# e0-dev-v004.net
KiCad netlist of a schematic drawn in EAGLE
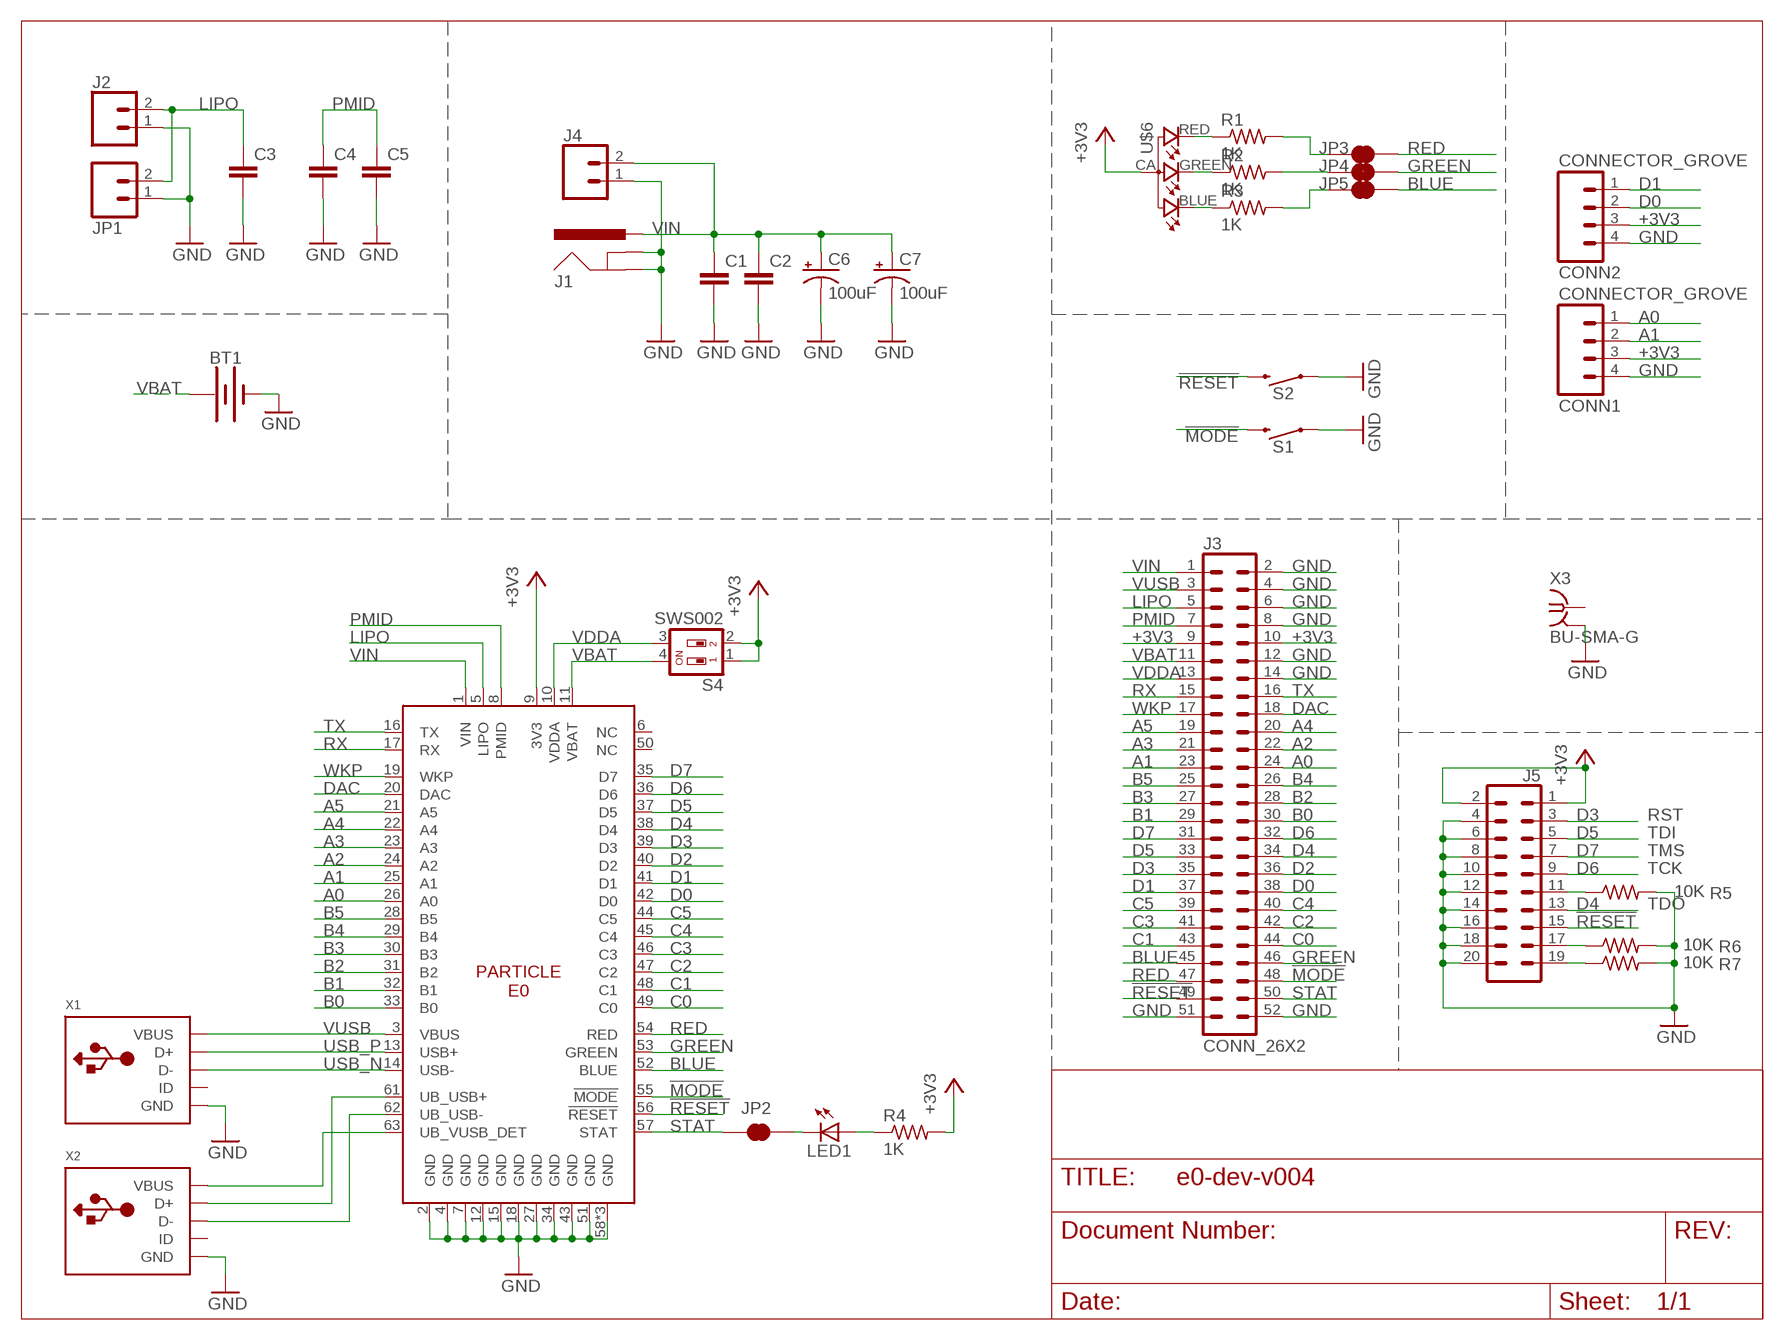
[diagram p0: schematic, sheet 1]

(export (version "E")
  (design (tool "Eeschema 10.0.6"))
  (components
    (comp (ref "BT1")
      (value "BATTERY-20MM_SMD")
      (footprint "eagle-import:BATTCON_20MM")
      (libsource (lib "eagle-import") (part "BATTERY-20MM_SMD"))
    )
    (comp (ref "C1")
      (value "C-EUC0805")
      (footprint "eagle-import:C0805")
      (libsource (lib "eagle-import") (part "C-EUC0805"))
    )
    (comp (ref "C2")
      (value "C-EUC0805")
      (footprint "eagle-import:C0805")
      (libsource (lib "eagle-import") (part "C-EUC0805"))
    )
    (comp (ref "C3")
      (value "C-EUC0805")
      (footprint "eagle-import:C0805")
      (libsource (lib "eagle-import") (part "C-EUC0805"))
    )
    (comp (ref "C4")
      (value "C-EUC0805")
      (footprint "eagle-import:C0805")
      (libsource (lib "eagle-import") (part "C-EUC0805"))
    )
    (comp (ref "C5")
      (value "C-EUC0805")
      (footprint "eagle-import:C0805")
      (libsource (lib "eagle-import") (part "C-EUC0805"))
    )
    (comp (ref "C6")
      (value "100uF")
      (footprint "eagle-import:PANASONIC_D")
      (libsource (lib "eagle-import") (part "100UF-POLAR-25V-20%(ELEC)"))
    )
    (comp (ref "C7")
      (value "100uF")
      (footprint "eagle-import:PANASONIC_D")
      (libsource (lib "eagle-import") (part "100UF-POLAR-25V-20%(ELEC)"))
    )
    (comp (ref "CONN1")
      (value "CONNECTOR_GROVE")
      (footprint "eagle-import:CONNCTOR_GROVE")
      (libsource (lib "eagle-import") (part "CONNECTOR_GROVE"))
    )
    (comp (ref "CONN2")
      (value "CONNECTOR_GROVE")
      (footprint "eagle-import:CONNCTOR_GROVE")
      (libsource (lib "eagle-import") (part "CONNECTOR_GROVE"))
    )
    (comp (ref "J1")
      (value "POWER_JACKSLT")
      (footprint "eagle-import:POWER_JACK_SLOT")
      (libsource (lib "eagle-import") (part "POWER_JACKSLT"))
    )
    (comp (ref "J2")
      (value "CONN_021X02_NO_SILK")
      (footprint "eagle-import:1X02_NO_SILK")
      (libsource (lib "eagle-import") (part "CONN_021X02_NO_SILK"))
    )
    (comp (ref "J3")
      (value "CONN_26X2")
      (footprint "eagle-import:2X26")
      (libsource (lib "eagle-import") (part "CONN_26X2"))
    )
    (comp (ref "J4")
      (value "CONN_021X02_NO_SILK")
      (footprint "eagle-import:1X02_NO_SILK")
      (libsource (lib "eagle-import") (part "CONN_021X02_NO_SILK"))
    )
    (comp (ref "J5")
      (value "CONN_10X2NOSILK")
      (footprint "eagle-import:2X10_NOSILK")
      (libsource (lib "eagle-import") (part "CONN_10X2NOSILK"))
    )
    (comp (ref "JP1")
      (value "M02-JST-2MM-SMT")
      (footprint "eagle-import:JST-2-SMD@1")
      (libsource (lib "eagle-import") (part "M02-JST-2MM-SMT"))
    )
    (comp (ref "JP2")
      (value "JUMPER-SMT_2_NC_TRACE_NO-SILK")
      (footprint "eagle-import:SMT-JUMPER_2_NC_TRACE_NO-SILK")
      (libsource (lib "eagle-import") (part "JUMPER-SMT_2_NC_TRACE_NO-SILK"))
    )
    (comp (ref "JP3")
      (value "JUMPER-SMT_2_NC_TRACE_NO-SILK")
      (footprint "eagle-import:SMT-JUMPER_2_NC_TRACE_NO-SILK")
      (libsource (lib "eagle-import") (part "JUMPER-SMT_2_NC_TRACE_NO-SILK"))
    )
    (comp (ref "JP4")
      (value "JUMPER-SMT_2_NC_TRACE_NO-SILK")
      (footprint "eagle-import:SMT-JUMPER_2_NC_TRACE_NO-SILK")
      (libsource (lib "eagle-import") (part "JUMPER-SMT_2_NC_TRACE_NO-SILK"))
    )
    (comp (ref "JP5")
      (value "JUMPER-SMT_2_NC_TRACE_NO-SILK")
      (footprint "eagle-import:SMT-JUMPER_2_NC_TRACE_NO-SILK")
      (libsource (lib "eagle-import") (part "JUMPER-SMT_2_NC_TRACE_NO-SILK"))
    )
    (comp (ref "LED1")
      (value "LED0603")
      (footprint "eagle-import:LED-0603")
      (libsource (lib "eagle-import") (part "LED0603"))
    )
    (comp (ref "R1")
      (value "1K")
      (footprint "eagle-import:R0603")
      (libsource (lib "eagle-import") (part "R-US_R0603"))
    )
    (comp (ref "R2")
      (value "1K")
      (footprint "eagle-import:R0603")
      (libsource (lib "eagle-import") (part "R-US_R0603"))
    )
    (comp (ref "R3")
      (value "1K")
      (footprint "eagle-import:R0603")
      (libsource (lib "eagle-import") (part "R-US_R0603"))
    )
    (comp (ref "R4")
      (value "1K")
      (footprint "eagle-import:R0603")
      (libsource (lib "eagle-import") (part "R-US_R0603"))
    )
    (comp (ref "R5")
      (value "10K")
      (footprint "eagle-import:R0603")
      (libsource (lib "eagle-import") (part "R-US_R0603"))
    )
    (comp (ref "R6")
      (value "10K")
      (footprint "eagle-import:R0603")
      (libsource (lib "eagle-import") (part "R-US_R0603"))
    )
    (comp (ref "R7")
      (value "10K")
      (footprint "eagle-import:R0603")
      (libsource (lib "eagle-import") (part "R-US_R0603"))
    )
    (comp (ref "S1")
      (value "MOMENTARY-SWITCH-SPST-SMD-5.2MM")
      (footprint "eagle-import:TACTILE_SWITCH_SMD_5.2MM")
      (libsource (lib "eagle-import") (part "MOMENTARY-SWITCH-SPST-SMD-5.2MM"))
    )
    (comp (ref "S2")
      (value "MOMENTARY-SWITCH-SPST-SMD-5.2MM")
      (footprint "eagle-import:TACTILE_SWITCH_SMD_5.2MM")
      (libsource (lib "eagle-import") (part "MOMENTARY-SWITCH-SPST-SMD-5.2MM"))
    )
    (comp (ref "S4")
      (value "SWS002")
      (footprint "eagle-import:SMS-002")
      (libsource (lib "eagle-import") (part "SWS002"))
    )
    (comp (ref "U$6")
      (value "RGB-LED-CLMVB-FKARGB")
      (footprint "eagle-import:PLCC4-2MM-RGB")
      (libsource (lib "eagle-import") (part "RGB-LED-CLMVB-FKARGB"))
    )
    (comp (ref "U1")
      (value "E0_V005")
      (footprint "eagle-import:E0")
      (libsource (lib "eagle-import") (part "E0_V005"))
    )
    (comp (ref "X1")
      (value "USB-NEW-PHOTON")
      (footprint "eagle-import:4UCONN_CMCUSB-5BFM14X-01-X")
      (libsource (lib "eagle-import") (part "USB-NEW-PHOTON"))
    )
    (comp (ref "X2")
      (value "USB-NEW-PHOTON")
      (footprint "eagle-import:4UCONN_CMCUSB-5BFM14X-01-X")
      (libsource (lib "eagle-import") (part "USB-NEW-PHOTON"))
    )
    (comp (ref "X3")
      (value "BU-SMA-G")
      (footprint "eagle-import:BU-SMA-G")
      (libsource (lib "eagle-import") (part "BU-SMA-G"))
    )
  )
  (nets
    (net (code "1") (name "+3V3") (class "Default")
      (node (ref "CONN1") (pin "3") (pinfunction "3_3") (pintype "passive"))
      (node (ref "CONN2") (pin "3") (pinfunction "3_3") (pintype "passive"))
      (node (ref "J3") (pin "10") (pinfunction "10_10") (pintype "passive"))
      (node (ref "J3") (pin "9") (pinfunction "9_9") (pintype "passive"))
      (node (ref "J5") (pin "1") (pinfunction "1_1") (pintype "passive"))
      (node (ref "J5") (pin "2") (pinfunction "2_2") (pintype "passive"))
      (node (ref "R4") (pin "2") (pinfunction "2_2") (pintype "passive"))
      (node (ref "S4") (pin "1") (pinfunction "1_1") (pintype "passive"))
      (node (ref "S4") (pin "2") (pinfunction "2_2") (pintype "passive"))
      (node (ref "U$6") (pin "CA") (pinfunction "1_CA") (pintype "passive"))
      (node (ref "U1") (pin "9") (pinfunction "3V3_9") (pintype "bidirectional"))
    )
    (net (code "2") (name "/A0") (class "Default")
      (node (ref "CONN1") (pin "1") (pinfunction "1_1") (pintype "passive"))
      (node (ref "J3") (pin "24") (pinfunction "24_24") (pintype "passive"))
      (node (ref "U1") (pin "26") (pinfunction "A0_26") (pintype "bidirectional"))
    )
    (net (code "3") (name "/A1") (class "Default")
      (node (ref "CONN1") (pin "2") (pinfunction "2_2") (pintype "passive"))
      (node (ref "J3") (pin "23") (pinfunction "23_23") (pintype "passive"))
      (node (ref "U1") (pin "25") (pinfunction "A1_25") (pintype "bidirectional"))
    )
    (net (code "4") (name "/A2") (class "Default")
      (node (ref "J3") (pin "22") (pinfunction "22_22") (pintype "passive"))
      (node (ref "U1") (pin "24") (pinfunction "A2_24") (pintype "bidirectional"))
    )
    (net (code "5") (name "/A3") (class "Default")
      (node (ref "J3") (pin "21") (pinfunction "21_21") (pintype "passive"))
      (node (ref "U1") (pin "23") (pinfunction "A3_23") (pintype "bidirectional"))
    )
    (net (code "6") (name "/A4") (class "Default")
      (node (ref "J3") (pin "20") (pinfunction "20_20") (pintype "passive"))
      (node (ref "U1") (pin "22") (pinfunction "A4_22") (pintype "bidirectional"))
    )
    (net (code "7") (name "/A5") (class "Default")
      (node (ref "J3") (pin "19") (pinfunction "19_19") (pintype "passive"))
      (node (ref "U1") (pin "21") (pinfunction "A5_21") (pintype "bidirectional"))
    )
    (net (code "8") (name "/B0") (class "Default")
      (node (ref "J3") (pin "30") (pinfunction "30_30") (pintype "passive"))
      (node (ref "U1") (pin "33") (pinfunction "B0_33") (pintype "bidirectional"))
    )
    (net (code "9") (name "/B1") (class "Default")
      (node (ref "J3") (pin "29") (pinfunction "29_29") (pintype "passive"))
      (node (ref "U1") (pin "32") (pinfunction "B1_32") (pintype "bidirectional"))
    )
    (net (code "10") (name "/B2") (class "Default")
      (node (ref "J3") (pin "28") (pinfunction "28_28") (pintype "passive"))
      (node (ref "U1") (pin "31") (pinfunction "B2_31") (pintype "bidirectional"))
    )
    (net (code "11") (name "/B3") (class "Default")
      (node (ref "J3") (pin "27") (pinfunction "27_27") (pintype "passive"))
      (node (ref "U1") (pin "30") (pinfunction "B3_30") (pintype "bidirectional"))
    )
    (net (code "12") (name "/B4") (class "Default")
      (node (ref "J3") (pin "26") (pinfunction "26_26") (pintype "passive"))
      (node (ref "U1") (pin "29") (pinfunction "B4_29") (pintype "bidirectional"))
    )
    (net (code "13") (name "/B5") (class "Default")
      (node (ref "J3") (pin "25") (pinfunction "25_25") (pintype "passive"))
      (node (ref "U1") (pin "28") (pinfunction "B5_28") (pintype "bidirectional"))
    )
    (net (code "14") (name "/BLUE") (class "Default")
      (node (ref "J3") (pin "45") (pinfunction "45_45") (pintype "passive"))
      (node (ref "JP5") (pin "2") (pinfunction "2_2") (pintype "passive"))
      (node (ref "U1") (pin "52") (pinfunction "BLUE_52") (pintype "bidirectional"))
    )
    (net (code "15") (name "/C0") (class "Default")
      (node (ref "J3") (pin "44") (pinfunction "44_44") (pintype "passive"))
      (node (ref "U1") (pin "49") (pinfunction "C0_49") (pintype "bidirectional"))
    )
    (net (code "16") (name "/C1") (class "Default")
      (node (ref "J3") (pin "43") (pinfunction "43_43") (pintype "passive"))
      (node (ref "U1") (pin "48") (pinfunction "C1_48") (pintype "bidirectional"))
    )
    (net (code "17") (name "/C2") (class "Default")
      (node (ref "J3") (pin "42") (pinfunction "42_42") (pintype "passive"))
      (node (ref "U1") (pin "47") (pinfunction "C2_47") (pintype "bidirectional"))
    )
    (net (code "18") (name "/C3") (class "Default")
      (node (ref "J3") (pin "41") (pinfunction "41_41") (pintype "passive"))
      (node (ref "U1") (pin "46") (pinfunction "C3_46") (pintype "bidirectional"))
    )
    (net (code "19") (name "/C4") (class "Default")
      (node (ref "J3") (pin "40") (pinfunction "40_40") (pintype "passive"))
      (node (ref "U1") (pin "45") (pinfunction "C4_45") (pintype "bidirectional"))
    )
    (net (code "20") (name "/C5") (class "Default")
      (node (ref "J3") (pin "39") (pinfunction "39_39") (pintype "passive"))
      (node (ref "U1") (pin "44") (pinfunction "C5_44") (pintype "bidirectional"))
    )
    (net (code "21") (name "/D0") (class "Default")
      (node (ref "CONN2") (pin "2") (pinfunction "2_2") (pintype "passive"))
      (node (ref "J3") (pin "38") (pinfunction "38_38") (pintype "passive"))
      (node (ref "U1") (pin "42") (pinfunction "D0_42") (pintype "bidirectional"))
    )
    (net (code "22") (name "/D1") (class "Default")
      (node (ref "CONN2") (pin "1") (pinfunction "1_1") (pintype "passive"))
      (node (ref "J3") (pin "37") (pinfunction "37_37") (pintype "passive"))
      (node (ref "U1") (pin "41") (pinfunction "D1_41") (pintype "bidirectional"))
    )
    (net (code "23") (name "/D2") (class "Default")
      (node (ref "J3") (pin "36") (pinfunction "36_36") (pintype "passive"))
      (node (ref "U1") (pin "40") (pinfunction "D2_40") (pintype "bidirectional"))
    )
    (net (code "24") (name "/D3") (class "Default")
      (node (ref "J3") (pin "35") (pinfunction "35_35") (pintype "passive"))
      (node (ref "J5") (pin "3") (pinfunction "3_3") (pintype "passive"))
      (node (ref "U1") (pin "39") (pinfunction "D3_39") (pintype "bidirectional"))
    )
    (net (code "25") (name "/D4") (class "Default")
      (node (ref "J3") (pin "34") (pinfunction "34_34") (pintype "passive"))
      (node (ref "J5") (pin "13") (pinfunction "13_13") (pintype "passive"))
      (node (ref "U1") (pin "38") (pinfunction "D4_38") (pintype "bidirectional"))
    )
    (net (code "26") (name "/D5") (class "Default")
      (node (ref "J3") (pin "33") (pinfunction "33_33") (pintype "passive"))
      (node (ref "J5") (pin "5") (pinfunction "5_5") (pintype "passive"))
      (node (ref "U1") (pin "37") (pinfunction "D5_37") (pintype "bidirectional"))
    )
    (net (code "27") (name "/D6") (class "Default")
      (node (ref "J3") (pin "32") (pinfunction "32_32") (pintype "passive"))
      (node (ref "J5") (pin "9") (pinfunction "9_9") (pintype "passive"))
      (node (ref "U1") (pin "36") (pinfunction "D6_36") (pintype "bidirectional"))
    )
    (net (code "28") (name "/D7") (class "Default")
      (node (ref "J3") (pin "31") (pinfunction "31_31") (pintype "passive"))
      (node (ref "J5") (pin "7") (pinfunction "7_7") (pintype "passive"))
      (node (ref "U1") (pin "35") (pinfunction "D7_35") (pintype "bidirectional"))
    )
    (net (code "29") (name "/DAC") (class "Default")
      (node (ref "J3") (pin "18") (pinfunction "18_18") (pintype "passive"))
      (node (ref "U1") (pin "20") (pinfunction "DAC_20") (pintype "bidirectional"))
    )
    (net (code "30") (name "/GREEN") (class "Default")
      (node (ref "J3") (pin "46") (pinfunction "46_46") (pintype "passive"))
      (node (ref "JP4") (pin "2") (pinfunction "2_2") (pintype "passive"))
      (node (ref "U1") (pin "53") (pinfunction "GREEN_53") (pintype "bidirectional"))
    )
    (net (code "31") (name "/LIPO") (class "Default")
      (node (ref "C3") (pin "1") (pinfunction "1_1") (pintype "passive"))
      (node (ref "J2") (pin "2") (pinfunction "2_2") (pintype "passive"))
      (node (ref "J3") (pin "5") (pinfunction "5_5") (pintype "passive"))
      (node (ref "JP1") (pin "2") (pinfunction "1_2") (pintype "passive"))
      (node (ref "U1") (pin "5") (pinfunction "LIPO_5") (pintype "bidirectional"))
    )
    (net (code "32") (name "/PMID") (class "Default")
      (node (ref "C4") (pin "1") (pinfunction "1_1") (pintype "passive"))
      (node (ref "C5") (pin "1") (pinfunction "1_1") (pintype "passive"))
      (node (ref "J3") (pin "7") (pinfunction "7_7") (pintype "passive"))
      (node (ref "U1") (pin "8") (pinfunction "PMID_8") (pintype "bidirectional"))
    )
    (net (code "33") (name "/RED") (class "Default")
      (node (ref "J3") (pin "47") (pinfunction "47_47") (pintype "passive"))
      (node (ref "JP3") (pin "2") (pinfunction "2_2") (pintype "passive"))
      (node (ref "U1") (pin "54") (pinfunction "RED_54") (pintype "bidirectional"))
    )
    (net (code "34") (name "/RX") (class "Default")
      (node (ref "J3") (pin "15") (pinfunction "15_15") (pintype "passive"))
      (node (ref "U1") (pin "17") (pinfunction "RX_17") (pintype "bidirectional"))
    )
    (net (code "35") (name "/STAT") (class "Default")
      (node (ref "J3") (pin "50") (pinfunction "50_50") (pintype "passive"))
      (node (ref "JP2") (pin "1") (pinfunction "1_1") (pintype "passive"))
      (node (ref "U1") (pin "57") (pinfunction "STAT_57") (pintype "bidirectional"))
    )
    (net (code "36") (name "/TX") (class "Default")
      (node (ref "J3") (pin "16") (pinfunction "16_16") (pintype "passive"))
      (node (ref "U1") (pin "16") (pinfunction "TX_16") (pintype "bidirectional"))
    )
    (net (code "37") (name "/USB_N") (class "Default")
      (node (ref "U1") (pin "14") (pinfunction "USB-_14") (pintype "bidirectional"))
      (node (ref "X1") (pin "P$4") (pinfunction "D-_P$4") (pintype "bidirectional"))
    )
    (net (code "38") (name "/USB_P") (class "Default")
      (node (ref "U1") (pin "13") (pinfunction "USB+_13") (pintype "bidirectional"))
      (node (ref "X1") (pin "P$3") (pinfunction "D+_P$3") (pintype "bidirectional"))
    )
    (net (code "39") (name "/VBAT") (class "Default")
      (node (ref "BT1") (pin "1") (pinfunction "+_1") (pintype "power_in"))
      (node (ref "J3") (pin "11") (pinfunction "11_11") (pintype "passive"))
      (node (ref "S4") (pin "4") (pinfunction "4_4") (pintype "passive"))
      (node (ref "U1") (pin "11") (pinfunction "VBAT_11") (pintype "bidirectional"))
    )
    (net (code "40") (name "/VDDA") (class "Default")
      (node (ref "J3") (pin "13") (pinfunction "13_13") (pintype "passive"))
      (node (ref "S4") (pin "3") (pinfunction "3_3") (pintype "passive"))
      (node (ref "U1") (pin "10") (pinfunction "VDDA_10") (pintype "bidirectional"))
    )
    (net (code "41") (name "/VIN") (class "Default")
      (node (ref "C1") (pin "1") (pinfunction "1_1") (pintype "passive"))
      (node (ref "C2") (pin "1") (pinfunction "1_1") (pintype "passive"))
      (node (ref "C6") (pin "+") (pinfunction "+_+") (pintype "passive"))
      (node (ref "C7") (pin "+") (pinfunction "+_+") (pintype "passive"))
      (node (ref "J1") (pin "PWR") (pinfunction "PWR_PWR") (pintype "bidirectional"))
      (node (ref "J3") (pin "1") (pinfunction "1_1") (pintype "passive"))
      (node (ref "J4") (pin "2") (pinfunction "2_2") (pintype "passive"))
      (node (ref "U1") (pin "1") (pinfunction "VIN_1") (pintype "bidirectional"))
    )
    (net (code "42") (name "/VUSB") (class "Default")
      (node (ref "J3") (pin "3") (pinfunction "3_3") (pintype "passive"))
      (node (ref "U1") (pin "3") (pinfunction "VBUS_3") (pintype "bidirectional"))
      (node (ref "X1") (pin "P$5") (pinfunction "VBUS_P$5") (pintype "power_in"))
    )
    (net (code "43") (name "/WKP") (class "Default")
      (node (ref "J3") (pin "17") (pinfunction "17_17") (pintype "passive"))
      (node (ref "U1") (pin "19") (pinfunction "WKP_19") (pintype "bidirectional"))
    )
    (net (code "44") (name "/~{MODE}") (class "Default")
      (node (ref "J3") (pin "48") (pinfunction "48_48") (pintype "passive"))
      (node (ref "S1") (pin "3") (pinfunction "2_3") (pintype "passive"))
      (node (ref "U1") (pin "55") (pinfunction "~{MODE}_55") (pintype "bidirectional"))
    )
    (net (code "45") (name "/~{RESET}") (class "Default")
      (node (ref "J3") (pin "49") (pinfunction "49_49") (pintype "passive"))
      (node (ref "J5") (pin "15") (pinfunction "15_15") (pintype "passive"))
      (node (ref "S2") (pin "3") (pinfunction "2_3") (pintype "passive"))
      (node (ref "U1") (pin "56") (pinfunction "~{RESET}_56") (pintype "bidirectional"))
    )
    (net (code "46") (name "GND") (class "Default")
      (node (ref "BT1") (pin "2") (pinfunction "-_2") (pintype "power_in"))
      (node (ref "C1") (pin "2") (pinfunction "2_2") (pintype "passive"))
      (node (ref "C2") (pin "2") (pinfunction "2_2") (pintype "passive"))
      (node (ref "C3") (pin "2") (pinfunction "2_2") (pintype "passive"))
      (node (ref "C4") (pin "2") (pinfunction "2_2") (pintype "passive"))
      (node (ref "C5") (pin "2") (pinfunction "2_2") (pintype "passive"))
      (node (ref "C6") (pin "-") (pinfunction "-_-") (pintype "passive"))
      (node (ref "C7") (pin "-") (pinfunction "-_-") (pintype "passive"))
      (node (ref "CONN1") (pin "4") (pinfunction "4_4") (pintype "passive"))
      (node (ref "CONN2") (pin "4") (pinfunction "4_4") (pintype "passive"))
      (node (ref "J1") (pin "GND@1") (pinfunction "GNDBREAK_GND@1") (pintype "bidirectional"))
      (node (ref "J1") (pin "GND@2") (pinfunction "GND_GND@2") (pintype "bidirectional"))
      (node (ref "J2") (pin "1") (pinfunction "1_1") (pintype "passive"))
      (node (ref "J3") (pin "12") (pinfunction "12_12") (pintype "passive"))
      (node (ref "J3") (pin "14") (pinfunction "14_14") (pintype "passive"))
      (node (ref "J3") (pin "2") (pinfunction "2_2") (pintype "passive"))
      (node (ref "J3") (pin "4") (pinfunction "4_4") (pintype "passive"))
      (node (ref "J3") (pin "51") (pinfunction "51_51") (pintype "passive"))
      (node (ref "J3") (pin "52") (pinfunction "52_52") (pintype "passive"))
      (node (ref "J3") (pin "6") (pinfunction "6_6") (pintype "passive"))
      (node (ref "J3") (pin "8") (pinfunction "8_8") (pintype "passive"))
      (node (ref "J4") (pin "1") (pinfunction "1_1") (pintype "passive"))
      (node (ref "J5") (pin "10") (pinfunction "10_10") (pintype "passive"))
      (node (ref "J5") (pin "12") (pinfunction "12_12") (pintype "passive"))
      (node (ref "J5") (pin "14") (pinfunction "14_14") (pintype "passive"))
      (node (ref "J5") (pin "16") (pinfunction "16_16") (pintype "passive"))
      (node (ref "J5") (pin "18") (pinfunction "18_18") (pintype "passive"))
      (node (ref "J5") (pin "20") (pinfunction "20_20") (pintype "passive"))
      (node (ref "J5") (pin "4") (pinfunction "4_4") (pintype "passive"))
      (node (ref "J5") (pin "6") (pinfunction "6_6") (pintype "passive"))
      (node (ref "J5") (pin "8") (pinfunction "8_8") (pintype "passive"))
      (node (ref "JP1") (pin "1") (pinfunction "2_1") (pintype "passive"))
      (node (ref "R5") (pin "2") (pinfunction "2_2") (pintype "passive"))
      (node (ref "R6") (pin "2") (pinfunction "2_2") (pintype "passive"))
      (node (ref "R7") (pin "2") (pinfunction "2_2") (pintype "passive"))
      (node (ref "S1") (pin "1") (pinfunction "1_1") (pintype "passive"))
      (node (ref "S2") (pin "1") (pinfunction "1_1") (pintype "passive"))
      (node (ref "U1") (pin "12") (pinfunction "GND_12") (pintype "bidirectional"))
      (node (ref "U1") (pin "15") (pinfunction "GND_15") (pintype "bidirectional"))
      (node (ref "U1") (pin "18") (pinfunction "GND_18") (pintype "bidirectional"))
      (node (ref "U1") (pin "2") (pinfunction "GND_2") (pintype "bidirectional"))
      (node (ref "U1") (pin "27") (pinfunction "GND_27") (pintype "bidirectional"))
      (node (ref "U1") (pin "34") (pinfunction "GND_34") (pintype "bidirectional"))
      (node (ref "U1") (pin "4") (pinfunction "GND_4") (pintype "bidirectional"))
      (node (ref "U1") (pin "43") (pinfunction "GND_43") (pintype "bidirectional"))
      (node (ref "U1") (pin "51") (pinfunction "GND_51") (pintype "bidirectional"))
      (node (ref "U1") (pin "58") (pinfunction "GND_58") (pintype "bidirectional"))
      (node (ref "U1") (pin "59") (pinfunction "GND_59") (pintype "bidirectional"))
      (node (ref "U1") (pin "60") (pinfunction "GND_60") (pintype "bidirectional"))
      (node (ref "U1") (pin "7") (pinfunction "GND_7") (pintype "bidirectional"))
      (node (ref "X1") (pin "P$1") (pinfunction "GND_P$1") (pintype "power_in"))
      (node (ref "X1") (pin "P$10") (pinfunction "GND_P$10") (pintype "power_in"))
      (node (ref "X1") (pin "P$11") (pinfunction "GND_P$11") (pintype "power_in"))
      (node (ref "X1") (pin "P$6") (pinfunction "GND_P$6") (pintype "power_in"))
      (node (ref "X1") (pin "P$7") (pinfunction "GND_P$7") (pintype "power_in"))
      (node (ref "X1") (pin "P$8") (pinfunction "GND_P$8") (pintype "power_in"))
      (node (ref "X1") (pin "P$9") (pinfunction "GND_P$9") (pintype "power_in"))
      (node (ref "X2") (pin "P$1") (pinfunction "GND_P$1") (pintype "power_in"))
      (node (ref "X2") (pin "P$10") (pinfunction "GND_P$10") (pintype "power_in"))
      (node (ref "X2") (pin "P$11") (pinfunction "GND_P$11") (pintype "power_in"))
      (node (ref "X2") (pin "P$6") (pinfunction "GND_P$6") (pintype "power_in"))
      (node (ref "X2") (pin "P$7") (pinfunction "GND_P$7") (pintype "power_in"))
      (node (ref "X2") (pin "P$8") (pinfunction "GND_P$8") (pintype "power_in"))
      (node (ref "X2") (pin "P$9") (pinfunction "GND_P$9") (pintype "power_in"))
      (node (ref "X3") (pin "2") (pinfunction "2_2") (pintype "passive"))
      (node (ref "X3") (pin "3") (pinfunction "2_3") (pintype "passive"))
      (node (ref "X3") (pin "4") (pinfunction "2_4") (pintype "passive"))
      (node (ref "X3") (pin "5") (pinfunction "2_5") (pintype "passive"))
    )
    (net (code "47") (name "Net-(J5-Pad11)") (class "Default")
      (node (ref "J5") (pin "11") (pinfunction "11_11") (pintype "passive"))
      (node (ref "R5") (pin "1") (pinfunction "1_1") (pintype "passive"))
    )
    (net (code "48") (name "Net-(J5-Pad17)") (class "Default")
      (node (ref "J5") (pin "17") (pinfunction "17_17") (pintype "passive"))
      (node (ref "R6") (pin "1") (pinfunction "1_1") (pintype "passive"))
    )
    (net (code "49") (name "Net-(J5-Pad19)") (class "Default")
      (node (ref "J5") (pin "19") (pinfunction "19_19") (pintype "passive"))
      (node (ref "R7") (pin "1") (pinfunction "1_1") (pintype "passive"))
    )
    (net (code "50") (name "Net-(JP2-Pad2)") (class "Default")
      (node (ref "JP2") (pin "2") (pinfunction "2_2") (pintype "passive"))
      (node (ref "LED1") (pin "C") (pinfunction "C_C") (pintype "passive"))
    )
    (net (code "51") (name "Net-(JP3-Pad1)") (class "Default")
      (node (ref "JP3") (pin "1") (pinfunction "1_1") (pintype "passive"))
      (node (ref "R1") (pin "2") (pinfunction "2_2") (pintype "passive"))
    )
    (net (code "52") (name "Net-(JP4-Pad1)") (class "Default")
      (node (ref "JP4") (pin "1") (pinfunction "1_1") (pintype "passive"))
      (node (ref "R2") (pin "2") (pinfunction "2_2") (pintype "passive"))
    )
    (net (code "53") (name "Net-(JP5-Pad1)") (class "Default")
      (node (ref "JP5") (pin "1") (pinfunction "1_1") (pintype "passive"))
      (node (ref "R3") (pin "2") (pinfunction "2_2") (pintype "passive"))
    )
    (net (code "54") (name "Net-(LED1-PadA)") (class "Default")
      (node (ref "LED1") (pin "A") (pinfunction "A_A") (pintype "passive"))
      (node (ref "R4") (pin "1") (pinfunction "1_1") (pintype "passive"))
    )
    (net (code "55") (name "Net-(U$6-2)") (class "Default")
      (node (ref "R3") (pin "1") (pinfunction "1_1") (pintype "passive"))
      (node (ref "U$6") (pin "BLUE") (pinfunction "2_BLUE") (pintype "passive"))
    )
    (net (code "56") (name "Net-(U$6-3)") (class "Default")
      (node (ref "R2") (pin "1") (pinfunction "1_1") (pintype "passive"))
      (node (ref "U$6") (pin "GREEN") (pinfunction "3_GREEN") (pintype "passive"))
    )
    (net (code "57") (name "Net-(U$6-4)") (class "Default")
      (node (ref "R1") (pin "1") (pinfunction "1_1") (pintype "passive"))
      (node (ref "U$6") (pin "RED") (pinfunction "4_RED") (pintype "passive"))
    )
    (net (code "58") (name "Net-(U1-UB_USB+)") (class "Default")
      (node (ref "U1") (pin "61") (pinfunction "UB_USB+_61") (pintype "bidirectional"))
      (node (ref "X2") (pin "P$3") (pinfunction "D+_P$3") (pintype "bidirectional"))
    )
    (net (code "59") (name "Net-(U1-UB_USB-)") (class "Default")
      (node (ref "U1") (pin "62") (pinfunction "UB_USB-_62") (pintype "bidirectional"))
      (node (ref "X2") (pin "P$4") (pinfunction "D-_P$4") (pintype "bidirectional"))
    )
    (net (code "60") (name "Net-(U1-UB_VUSB_DET)") (class "Default")
      (node (ref "U1") (pin "63") (pinfunction "UB_VUSB_DET_63") (pintype "bidirectional"))
      (node (ref "X2") (pin "P$5") (pinfunction "VBUS_P$5") (pintype "power_in"))
    )
    (net (code "61") (name "unconnected-(U1-NC-Pad6)") (class "Default")
      (node (ref "U1") (pin "6") (pinfunction "NC_6") (pintype "bidirectional"))
    )
    (net (code "62") (name "unconnected-(U1-NC-Pad50)") (class "Default")
      (node (ref "U1") (pin "50") (pinfunction "NC_50") (pintype "bidirectional"))
    )
    (net (code "63") (name "unconnected-(X1-ID-PadP$2)") (class "Default")
      (node (ref "X1") (pin "P$2") (pinfunction "ID_P$2") (pintype "bidirectional"))
    )
    (net (code "64") (name "unconnected-(X2-ID-PadP$2)") (class "Default")
      (node (ref "X2") (pin "P$2") (pinfunction "ID_P$2") (pintype "bidirectional"))
    )
    (net (code "65") (name "unconnected-(X3-Pad1)") (class "Default")
      (node (ref "X3") (pin "1") (pinfunction "1_1") (pintype "passive"))
    )
  )
)
